# ACCUM-POWER.net
KiCad netlist of a schematic drawn in EAGLE
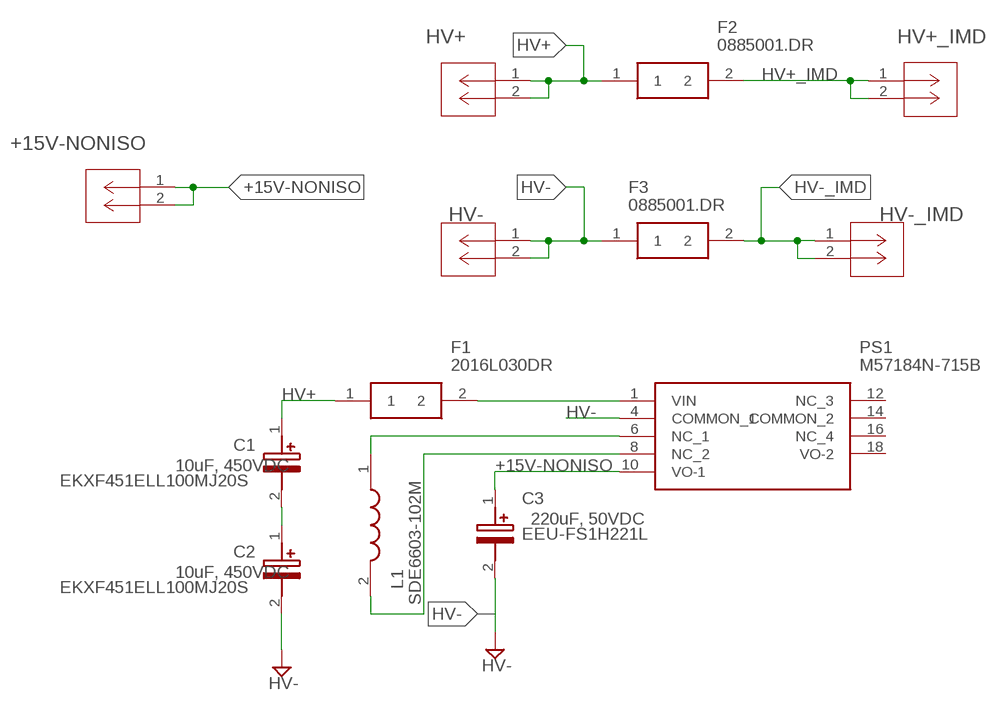
[diagram p0: schematic, sheet 1]

(export (version "E")
  (design (tool "Eeschema 10.0.6"))
  (components
    (comp (ref "+15V-NONISO")
      (value "2P(90DEG)_1-770966-0")
      (footprint "eagle-import:CON2_1X2_P163_RAMNL")
      (fields (field (name "MANUFACTURER_PART_NUMBER") "17709660"))
      (libsource (lib "eagle-import") (part "2P(90DEG)_1-770966-0"))
    )
    (comp (ref "C1")
      (value "EKXF451ELL100MJ20S")
      (footprint "eagle-import:CAPPRD500W60D1025H2150")
      (fields (field (name "MOUSER_PART_NUMBER") "661-EKXF451ELL100MJ2"))
      (libsource (lib "eagle-import") (part "EKXF451ELL100MJ20S"))
    )
    (comp (ref "C2")
      (value "EKXF451ELL100MJ20S")
      (footprint "eagle-import:CAPPRD500W60D1025H2150")
      (fields (field (name "MOUSER_PART_NUMBER") "661-EKXF451ELL100MJ2"))
      (libsource (lib "eagle-import") (part "EKXF451ELL100MJ20S"))
    )
    (comp (ref "C3")
      (value "EEU-FS1H221L")
      (footprint "eagle-import:CAPPRD350W65D800H2200")
      (fields (field (name "MOUSER_PART_NUMBER") "667-EEU-FS1H221L"))
      (libsource (lib "eagle-import") (part "EEU-FS1H221L"))
    )
    (comp (ref "F1")
      (value "2016L030DR")
      (footprint "eagle-import:FUSC5141X125N")
      (fields (field (name "MOUSER_PART_NUMBER") "576-2016L030DR"))
      (libsource (lib "eagle-import") (part "2016L030DR"))
    )
    (comp (ref "F2")
      (value "0885001.DR")
      (footprint "eagle-import:FUSC10948X488N")
      (fields (field (name "MOUSER_PART_NUMBER") "576-0885001.DR"))
      (libsource (lib "eagle-import") (part "0885001.DR"))
    )
    (comp (ref "F3")
      (value "0885001.DR")
      (footprint "eagle-import:FUSC10948X488N")
      (fields (field (name "MOUSER_PART_NUMBER") "576-0885001.DR"))
      (libsource (lib "eagle-import") (part "0885001.DR"))
    )
    (comp (ref "HV+")
      (value "2P(90DEG)_1-770966-0")
      (footprint "eagle-import:CON2_1X2_P163_RAMNL")
      (fields (field (name "MANUFACTURER_PART_NUMBER") "17709660"))
      (libsource (lib "eagle-import") (part "2P(90DEG)_1-770966-0"))
    )
    (comp (ref "HV+_IMD")
      (value "2P(90DEG)_1-770966-0")
      (footprint "eagle-import:CON2_1X2_P163_RAMNL")
      (fields (field (name "MANUFACTURER_PART_NUMBER") "17709660"))
      (libsource (lib "eagle-import") (part "2P(90DEG)_1-770966-0"))
    )
    (comp (ref "HV-")
      (value "2P(90DEG)_1-770966-0")
      (footprint "eagle-import:CON2_1X2_P163_RAMNL")
      (fields (field (name "MANUFACTURER_PART_NUMBER") "17709660"))
      (libsource (lib "eagle-import") (part "2P(90DEG)_1-770966-0"))
    )
    (comp (ref "HV-_IMD")
      (value "2P(90DEG)_1-770966-0")
      (footprint "eagle-import:CON2_1X2_P163_RAMNL")
      (fields (field (name "MANUFACTURER_PART_NUMBER") "17709660"))
      (libsource (lib "eagle-import") (part "2P(90DEG)_1-770966-0"))
    )
    (comp (ref "L1")
      (value "SDE6603-102M")
      (footprint "eagle-import:SDE6603")
      (fields (field (name "MOUSER_PART_NUMBER") "652-SDE6603-102M"))
      (libsource (lib "eagle-import") (part "SDE6603-102M"))
    )
    (comp (ref "PS1")
      (value "M57184N-715B")
      (footprint "eagle-import:M57184N715B")
      (libsource (lib "eagle-import") (part "M57184N-715B"))
    )
  )
  (nets
    (net (code "1") (name "+15V-NONISO") (class "Default")
      (node (ref "+15V-NONISO") (pin "1") (pinfunction "1_1") (pintype "passive"))
      (node (ref "+15V-NONISO") (pin "2") (pinfunction "2_2") (pintype "passive"))
      (node (ref "C3") (pin "1") (pinfunction "+_1") (pintype "bidirectional"))
      (node (ref "PS1") (pin "10") (pinfunction "VO-1_10") (pintype "bidirectional"))
    )
    (net (code "2") (name "/HV+_IMD") (class "Default")
      (node (ref "F2") (pin "2") (pinfunction "2_2") (pintype "bidirectional"))
      (node (ref "HV+_IMD") (pin "1") (pinfunction "1_1") (pintype "passive"))
      (node (ref "HV+_IMD") (pin "2") (pinfunction "2_2") (pintype "passive"))
    )
    (net (code "3") (name "HV+") (class "Default")
      (node (ref "C1") (pin "1") (pinfunction "+_1") (pintype "bidirectional"))
      (node (ref "F1") (pin "1") (pinfunction "1_1") (pintype "bidirectional"))
      (node (ref "F2") (pin "1") (pinfunction "1_1") (pintype "bidirectional"))
      (node (ref "HV+") (pin "1") (pinfunction "1_1") (pintype "passive"))
      (node (ref "HV+") (pin "2") (pinfunction "2_2") (pintype "passive"))
    )
    (net (code "4") (name "HV-") (class "Default")
      (node (ref "C2") (pin "2") (pinfunction "-_2") (pintype "bidirectional"))
      (node (ref "C3") (pin "2") (pinfunction "-_2") (pintype "bidirectional"))
      (node (ref "F3") (pin "1") (pinfunction "1_1") (pintype "bidirectional"))
      (node (ref "HV-") (pin "1") (pinfunction "1_1") (pintype "passive"))
      (node (ref "HV-") (pin "2") (pinfunction "2_2") (pintype "passive"))
      (node (ref "PS1") (pin "4") (pinfunction "COMMON_1_4") (pintype "bidirectional"))
    )
    (net (code "5") (name "HV-_IMD") (class "Default")
      (node (ref "F3") (pin "2") (pinfunction "2_2") (pintype "bidirectional"))
      (node (ref "HV-_IMD") (pin "1") (pinfunction "1_1") (pintype "passive"))
      (node (ref "HV-_IMD") (pin "2") (pinfunction "2_2") (pintype "passive"))
    )
    (net (code "6") (name "Net-(C1--)") (class "Default")
      (node (ref "C1") (pin "2") (pinfunction "-_2") (pintype "bidirectional"))
      (node (ref "C2") (pin "1") (pinfunction "+_1") (pintype "bidirectional"))
    )
    (net (code "7") (name "Net-(PS1-NC_1)") (class "Default")
      (node (ref "L1") (pin "1") (pinfunction "1_1") (pintype "bidirectional"))
      (node (ref "PS1") (pin "6") (pinfunction "NC_1_6") (pintype "bidirectional"))
    )
    (net (code "8") (name "Net-(PS1-NC_2)") (class "Default")
      (node (ref "L1") (pin "2") (pinfunction "2_2") (pintype "bidirectional"))
      (node (ref "PS1") (pin "8") (pinfunction "NC_2_8") (pintype "bidirectional"))
    )
    (net (code "9") (name "Net-(PS1-VIN)") (class "Default")
      (node (ref "F1") (pin "2") (pinfunction "2_2") (pintype "bidirectional"))
      (node (ref "PS1") (pin "1") (pinfunction "VIN_1") (pintype "bidirectional"))
    )
    (net (code "10") (name "unconnected-(PS1-COMMON_2-Pad14)") (class "Default")
      (node (ref "PS1") (pin "14") (pinfunction "COMMON_2_14") (pintype "bidirectional"))
    )
    (net (code "11") (name "unconnected-(PS1-NC_3-Pad12)") (class "Default")
      (node (ref "PS1") (pin "12") (pinfunction "NC_3_12") (pintype "bidirectional"))
    )
    (net (code "12") (name "unconnected-(PS1-NC_4-Pad16)") (class "Default")
      (node (ref "PS1") (pin "16") (pinfunction "NC_4_16") (pintype "bidirectional"))
    )
    (net (code "13") (name "unconnected-(PS1-VO-2-Pad18)") (class "Default")
      (node (ref "PS1") (pin "18") (pinfunction "VO-2_18") (pintype "bidirectional"))
    )
  )
)
